# hand-held-controller.net
KiCad netlist of a schematic drawn in EAGLE
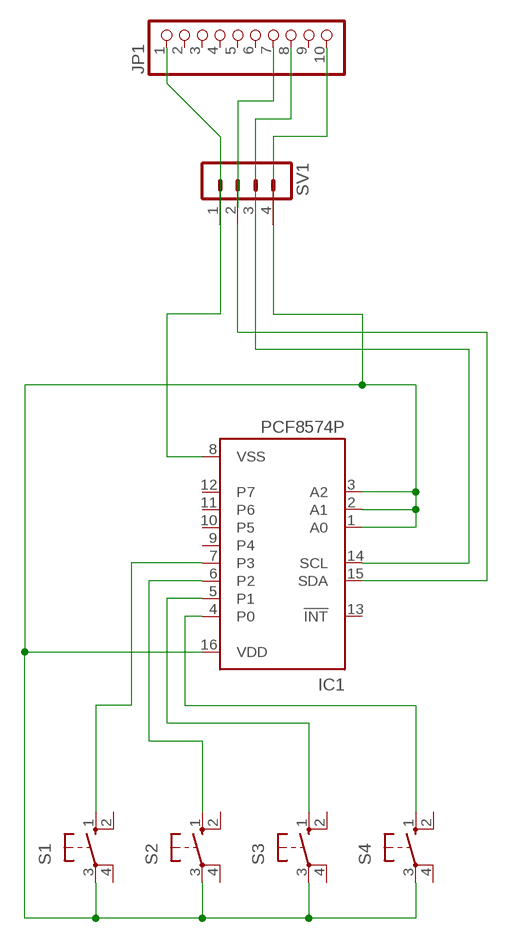
[diagram p0: schematic, sheet 1]

(export (version "E")
  (design (tool "Eeschema 10.0.6"))
  (components
    (comp (ref "IC1")
      (value "PCF8574P")
      (footprint "eagle-import:DIL16")
      (fields (field (name "MPN") "PCF8574PN"))
      (libsource (lib "eagle-import") (part "PCF8574P"))
    )
    (comp (ref "JP1")
      (value "PINHD-1X10")
      (footprint "eagle-import:1X10")
      (libsource (lib "eagle-import") (part "PINHD-1X10"))
    )
    (comp (ref "S1")
      (value "10-XX")
      (footprint "eagle-import:B3F-10XX")
      (fields (field (name "MPN") "B3F-1000"))
      (libsource (lib "eagle-import") (part "10-XX"))
    )
    (comp (ref "S2")
      (value "10-XX")
      (footprint "eagle-import:B3F-10XX")
      (fields (field (name "MPN") "B3F-1000"))
      (libsource (lib "eagle-import") (part "10-XX"))
    )
    (comp (ref "S3")
      (value "10-XX")
      (footprint "eagle-import:B3F-10XX")
      (fields (field (name "MPN") "B3F-1000"))
      (libsource (lib "eagle-import") (part "10-XX"))
    )
    (comp (ref "S4")
      (value "10-XX")
      (footprint "eagle-import:B3F-10XX")
      (fields (field (name "MPN") "B3F-1000"))
      (libsource (lib "eagle-import") (part "10-XX"))
    )
    (comp (ref "SV1")
      (value "MA04-1")
      (footprint "eagle-import:MA04-1")
      (libsource (lib "eagle-import") (part "MA04-1"))
    )
  )
  (nets
    (net (code "1") (name "Net-(IC1-A0)") (class "Default")
      (node (ref "IC1") (pin "1") (pinfunction "A0_1") (pintype "input"))
      (node (ref "IC1") (pin "16") (pinfunction "VDD_16") (pintype "power_in"))
      (node (ref "IC1") (pin "2") (pinfunction "A1_2") (pintype "input"))
      (node (ref "IC1") (pin "3") (pinfunction "A2_3") (pintype "input"))
      (node (ref "JP1") (pin "10") (pinfunction "10_10") (pintype "passive"))
      (node (ref "S1") (pin "3") (pinfunction "P_3") (pintype "passive"))
      (node (ref "S2") (pin "3") (pinfunction "P_3") (pintype "passive"))
      (node (ref "S3") (pin "3") (pinfunction "P_3") (pintype "passive"))
      (node (ref "S4") (pin "3") (pinfunction "P_3") (pintype "passive"))
      (node (ref "SV1") (pin "4") (pinfunction "4_4") (pintype "passive"))
    )
    (net (code "2") (name "Net-(IC1-P0)") (class "Default")
      (node (ref "IC1") (pin "4") (pinfunction "P0_4") (pintype "bidirectional"))
      (node (ref "S4") (pin "1") (pinfunction "S_1") (pintype "passive"))
    )
    (net (code "3") (name "Net-(IC1-P1)") (class "Default")
      (node (ref "IC1") (pin "5") (pinfunction "P1_5") (pintype "bidirectional"))
      (node (ref "S3") (pin "1") (pinfunction "S_1") (pintype "passive"))
    )
    (net (code "4") (name "Net-(IC1-P2)") (class "Default")
      (node (ref "IC1") (pin "6") (pinfunction "P2_6") (pintype "bidirectional"))
      (node (ref "S2") (pin "1") (pinfunction "S_1") (pintype "passive"))
    )
    (net (code "5") (name "Net-(IC1-P3)") (class "Default")
      (node (ref "IC1") (pin "7") (pinfunction "P3_7") (pintype "bidirectional"))
      (node (ref "S1") (pin "1") (pinfunction "S_1") (pintype "passive"))
    )
    (net (code "6") (name "Net-(IC1-SCL)") (class "Default")
      (node (ref "IC1") (pin "14") (pinfunction "SCL_14") (pintype "input"))
      (node (ref "JP1") (pin "8") (pinfunction "8_8") (pintype "passive"))
      (node (ref "SV1") (pin "3") (pinfunction "3_3") (pintype "passive"))
    )
    (net (code "7") (name "Net-(IC1-SDA)") (class "Default")
      (node (ref "IC1") (pin "15") (pinfunction "SDA_15") (pintype "bidirectional"))
      (node (ref "SV1") (pin "2") (pinfunction "2_2") (pintype "passive"))
    )
    (net (code "8") (name "Net-(IC1-VSS)") (class "Default")
      (node (ref "IC1") (pin "8") (pinfunction "VSS_8") (pintype "power_in"))
      (node (ref "JP1") (pin "1") (pinfunction "1_1") (pintype "passive"))
      (node (ref "SV1") (pin "1") (pinfunction "1_1") (pintype "passive"))
    )
    (net (code "9") (name "unconnected-(IC1-P4-Pad9)") (class "Default")
      (node (ref "IC1") (pin "9") (pinfunction "P4_9") (pintype "bidirectional"))
    )
    (net (code "10") (name "unconnected-(IC1-P5-Pad10)") (class "Default")
      (node (ref "IC1") (pin "10") (pinfunction "P5_10") (pintype "bidirectional"))
    )
    (net (code "11") (name "unconnected-(IC1-P6-Pad11)") (class "Default")
      (node (ref "IC1") (pin "11") (pinfunction "P6_11") (pintype "bidirectional"))
    )
    (net (code "12") (name "unconnected-(IC1-P7-Pad12)") (class "Default")
      (node (ref "IC1") (pin "12") (pinfunction "P7_12") (pintype "bidirectional"))
    )
    (net (code "13") (name "unconnected-(IC1-~{INT}-Pad13)") (class "Default")
      (node (ref "IC1") (pin "13") (pinfunction "~{INT}_13") (pintype "output"))
    )
    (net (code "14") (name "unconnected-(JP1-Pad2)") (class "Default")
      (node (ref "JP1") (pin "2") (pinfunction "2_2") (pintype "passive"))
    )
    (net (code "15") (name "unconnected-(JP1-Pad3)") (class "Default")
      (node (ref "JP1") (pin "3") (pinfunction "3_3") (pintype "passive"))
    )
    (net (code "16") (name "unconnected-(JP1-Pad4)") (class "Default")
      (node (ref "JP1") (pin "4") (pinfunction "4_4") (pintype "passive"))
    )
    (net (code "17") (name "unconnected-(JP1-Pad5)") (class "Default")
      (node (ref "JP1") (pin "5") (pinfunction "5_5") (pintype "passive"))
    )
    (net (code "18") (name "unconnected-(JP1-Pad6)") (class "Default")
      (node (ref "JP1") (pin "6") (pinfunction "6_6") (pintype "passive"))
    )
    (net (code "19") (name "unconnected-(JP1-Pad7)") (class "Default")
      (node (ref "JP1") (pin "7") (pinfunction "7_7") (pintype "passive"))
    )
    (net (code "20") (name "unconnected-(JP1-Pad9)") (class "Default")
      (node (ref "JP1") (pin "9") (pinfunction "9_9") (pintype "passive"))
    )
    (net (code "21") (name "unconnected-(S1-P1-Pad4)") (class "Default")
      (node (ref "S1") (pin "4") (pinfunction "P1_4") (pintype "passive"))
    )
    (net (code "22") (name "unconnected-(S1-S1-Pad2)") (class "Default")
      (node (ref "S1") (pin "2") (pinfunction "S1_2") (pintype "passive"))
    )
    (net (code "23") (name "unconnected-(S2-P1-Pad4)") (class "Default")
      (node (ref "S2") (pin "4") (pinfunction "P1_4") (pintype "passive"))
    )
    (net (code "24") (name "unconnected-(S2-S1-Pad2)") (class "Default")
      (node (ref "S2") (pin "2") (pinfunction "S1_2") (pintype "passive"))
    )
    (net (code "25") (name "unconnected-(S3-P1-Pad4)") (class "Default")
      (node (ref "S3") (pin "4") (pinfunction "P1_4") (pintype "passive"))
    )
    (net (code "26") (name "unconnected-(S3-S1-Pad2)") (class "Default")
      (node (ref "S3") (pin "2") (pinfunction "S1_2") (pintype "passive"))
    )
    (net (code "27") (name "unconnected-(S4-P1-Pad4)") (class "Default")
      (node (ref "S4") (pin "4") (pinfunction "P1_4") (pintype "passive"))
    )
    (net (code "28") (name "unconnected-(S4-S1-Pad2)") (class "Default")
      (node (ref "S4") (pin "2") (pinfunction "S1_2") (pintype "passive"))
    )
  )
)
